# working.net
KiCad netlist of a schematic drawn in EAGLE
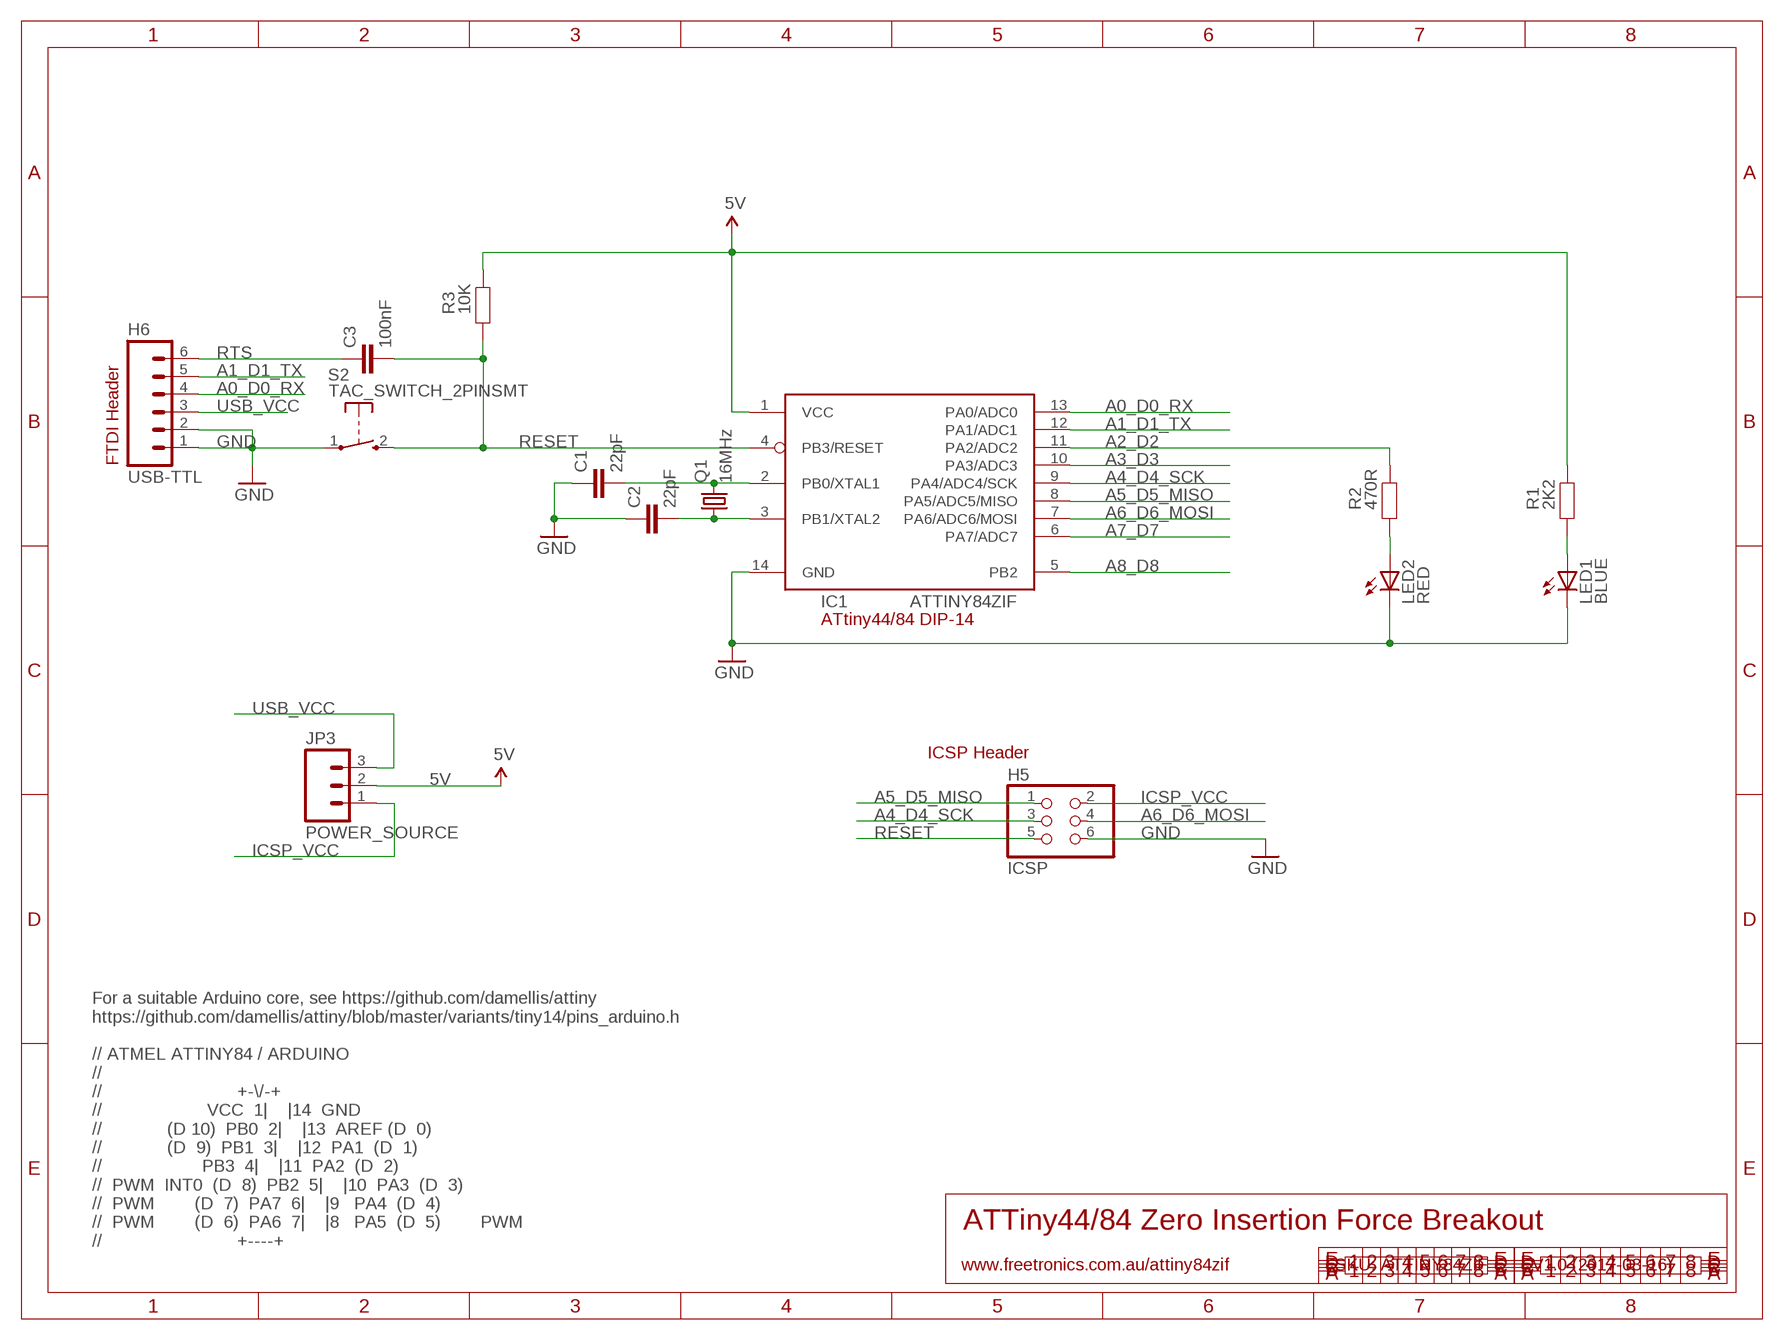
[diagram p0: schematic, sheet 1]

(export (version "E")
  (design (tool "Eeschema 10.0.6"))
  (components
    (comp (ref "C1")
      (value "22pF")
      (footprint "eagle-import:0603")
      (libsource (lib "eagle-import") (part "CAP0603"))
    )
    (comp (ref "C2")
      (value "22pF")
      (footprint "eagle-import:0603")
      (libsource (lib "eagle-import") (part "CAP0603"))
    )
    (comp (ref "C3")
      (value "100nF")
      (footprint "eagle-import:0603")
      (libsource (lib "eagle-import") (part "CAP0603"))
    )
    (comp (ref "H5")
      (value "ICSP")
      (footprint "eagle-import:2X03")
      (libsource (lib "eagle-import") (part "PINHD-2X3"))
    )
    (comp (ref "H6")
      (value "USB-TTL")
      (footprint "eagle-import:1X06")
      (libsource (lib "eagle-import") (part "M06SIP"))
    )
    (comp (ref "IC1")
      (value "ATTINY84ZIF")
      (footprint "eagle-import:DIL14-3-ZIF")
      (libsource (lib "eagle-import") (part "ATTINY84ZIF"))
    )
    (comp (ref "JP3")
      (value "POWER_SOURCE")
      (footprint "eagle-import:1X03")
      (libsource (lib "eagle-import") (part "M03PTH"))
    )
    (comp (ref "LED1")
      (value "BLUE")
      (footprint "eagle-import:LED-0603")
      (libsource (lib "eagle-import") (part "LED0603"))
    )
    (comp (ref "LED2")
      (value "RED")
      (footprint "eagle-import:LED-0603")
      (libsource (lib "eagle-import") (part "LED0603"))
    )
    (comp (ref "Q1")
      (value "16MHz")
      (footprint "eagle-import:HC49US")
      (libsource (lib "eagle-import") (part "CRYSTALHC49US"))
    )
    (comp (ref "R1")
      (value "2K2")
      (footprint "eagle-import:0603")
      (libsource (lib "eagle-import") (part "RESISTOR0603"))
    )
    (comp (ref "R2")
      (value "470R")
      (footprint "eagle-import:0603")
      (libsource (lib "eagle-import") (part "RESISTOR0603"))
    )
    (comp (ref "R3")
      (value "10K")
      (footprint "eagle-import:0603")
      (libsource (lib "eagle-import") (part "RESISTOR0603"))
    )
    (comp (ref "S2")
      (value "TAC_SWITCH_2PINSMT")
      (footprint "eagle-import:TACTILE_SWITCH_SMD_2PIN_TINY")
      (libsource (lib "eagle-import") (part "TAC_SWITCH_2PINSMT"))
    )
  )
  (nets
    (net (code "1") (name "/A0_D0_RX") (class "Default")
      (node (ref "H6") (pin "4") (pinfunction "4_4") (pintype "passive"))
      (node (ref "IC1") (pin "13") (pinfunction "PA0/ADC0_13") (pintype "bidirectional"))
    )
    (net (code "2") (name "/A1_D1_TX") (class "Default")
      (node (ref "H6") (pin "5") (pinfunction "5_5") (pintype "passive"))
      (node (ref "IC1") (pin "12") (pinfunction "PA1/ADC1_12") (pintype "bidirectional"))
    )
    (net (code "3") (name "/A2_D2") (class "Default")
      (node (ref "IC1") (pin "11") (pinfunction "PA2/ADC2_11") (pintype "bidirectional"))
      (node (ref "R2") (pin "2") (pinfunction "2_2") (pintype "passive"))
    )
    (net (code "4") (name "/A3_D3") (class "Default")
      (node (ref "IC1") (pin "10") (pinfunction "PA3/ADC3_10") (pintype "bidirectional"))
    )
    (net (code "5") (name "/A4_D4_SCK") (class "Default")
      (node (ref "H5") (pin "3") (pinfunction "3_3") (pintype "passive"))
      (node (ref "IC1") (pin "9") (pinfunction "PA4/ADC4/SCK_9") (pintype "bidirectional"))
    )
    (net (code "6") (name "/A5_D5_MISO") (class "Default")
      (node (ref "H5") (pin "1") (pinfunction "1_1") (pintype "passive"))
      (node (ref "IC1") (pin "8") (pinfunction "PA5/ADC5/MISO_8") (pintype "bidirectional"))
    )
    (net (code "7") (name "/A6_D6_MOSI") (class "Default")
      (node (ref "H5") (pin "4") (pinfunction "4_4") (pintype "passive"))
      (node (ref "IC1") (pin "7") (pinfunction "PA6/ADC6/MOSI_7") (pintype "bidirectional"))
    )
    (net (code "8") (name "/A7_D7") (class "Default")
      (node (ref "IC1") (pin "6") (pinfunction "PA7/ADC7_6") (pintype "bidirectional"))
    )
    (net (code "9") (name "/A8_D8") (class "Default")
      (node (ref "IC1") (pin "5") (pinfunction "PB2_5") (pintype "bidirectional"))
    )
    (net (code "10") (name "/ICSP_VCC") (class "Default")
      (node (ref "H5") (pin "2") (pinfunction "2_2") (pintype "passive"))
      (node (ref "JP3") (pin "1") (pinfunction "1_1") (pintype "passive"))
    )
    (net (code "11") (name "/RESET") (class "Default")
      (node (ref "C3") (pin "2") (pinfunction "2_2") (pintype "passive"))
      (node (ref "H5") (pin "5") (pinfunction "5_5") (pintype "passive"))
      (node (ref "IC1") (pin "4") (pinfunction "PB3/RESET_4") (pintype "bidirectional"))
      (node (ref "R3") (pin "1") (pinfunction "1_1") (pintype "passive"))
      (node (ref "S2") (pin "2") (pinfunction "S_2") (pintype "passive"))
    )
    (net (code "12") (name "/RTS") (class "Default")
      (node (ref "C3") (pin "1") (pinfunction "1_1") (pintype "passive"))
      (node (ref "H6") (pin "6") (pinfunction "6_6") (pintype "passive"))
    )
    (net (code "13") (name "/USB_VCC") (class "Default")
      (node (ref "H6") (pin "3") (pinfunction "3_3") (pintype "passive"))
      (node (ref "JP3") (pin "3") (pinfunction "3_3") (pintype "passive"))
    )
    (net (code "14") (name "5V") (class "Default")
      (node (ref "IC1") (pin "1") (pinfunction "VCC_1") (pintype "bidirectional"))
      (node (ref "JP3") (pin "2") (pinfunction "2_2") (pintype "passive"))
      (node (ref "R1") (pin "2") (pinfunction "2_2") (pintype "passive"))
      (node (ref "R3") (pin "2") (pinfunction "2_2") (pintype "passive"))
    )
    (net (code "15") (name "GND") (class "Default")
      (node (ref "C1") (pin "1") (pinfunction "1_1") (pintype "passive"))
      (node (ref "C2") (pin "1") (pinfunction "1_1") (pintype "passive"))
      (node (ref "H5") (pin "6") (pinfunction "6_6") (pintype "passive"))
      (node (ref "H6") (pin "1") (pinfunction "1_1") (pintype "passive"))
      (node (ref "H6") (pin "2") (pinfunction "2_2") (pintype "passive"))
      (node (ref "IC1") (pin "14") (pinfunction "GND_14") (pintype "bidirectional"))
      (node (ref "LED1") (pin "C") (pinfunction "C_C") (pintype "passive"))
      (node (ref "LED2") (pin "C") (pinfunction "C_C") (pintype "passive"))
      (node (ref "S2") (pin "1") (pinfunction "P_1") (pintype "passive"))
    )
    (net (code "16") (name "Net-(IC1-PB0{slash}XTAL1)") (class "Default")
      (node (ref "C1") (pin "2") (pinfunction "2_2") (pintype "passive"))
      (node (ref "IC1") (pin "2") (pinfunction "PB0/XTAL1_2") (pintype "bidirectional"))
      (node (ref "Q1") (pin "2") (pinfunction "2_2") (pintype "passive"))
    )
    (net (code "17") (name "Net-(IC1-PB1{slash}XTAL2)") (class "Default")
      (node (ref "C2") (pin "2") (pinfunction "2_2") (pintype "passive"))
      (node (ref "IC1") (pin "3") (pinfunction "PB1/XTAL2_3") (pintype "bidirectional"))
      (node (ref "Q1") (pin "1") (pinfunction "1_1") (pintype "passive"))
    )
    (net (code "18") (name "Net-(LED1-PadA)") (class "Default")
      (node (ref "LED1") (pin "A") (pinfunction "A_A") (pintype "passive"))
      (node (ref "R1") (pin "1") (pinfunction "1_1") (pintype "passive"))
    )
    (net (code "19") (name "Net-(LED2-PadA)") (class "Default")
      (node (ref "LED2") (pin "A") (pinfunction "A_A") (pintype "passive"))
      (node (ref "R2") (pin "1") (pinfunction "1_1") (pintype "passive"))
    )
  )
)
